# mains_relay_modem.net
KiCad netlist of a schematic drawn in EAGLE
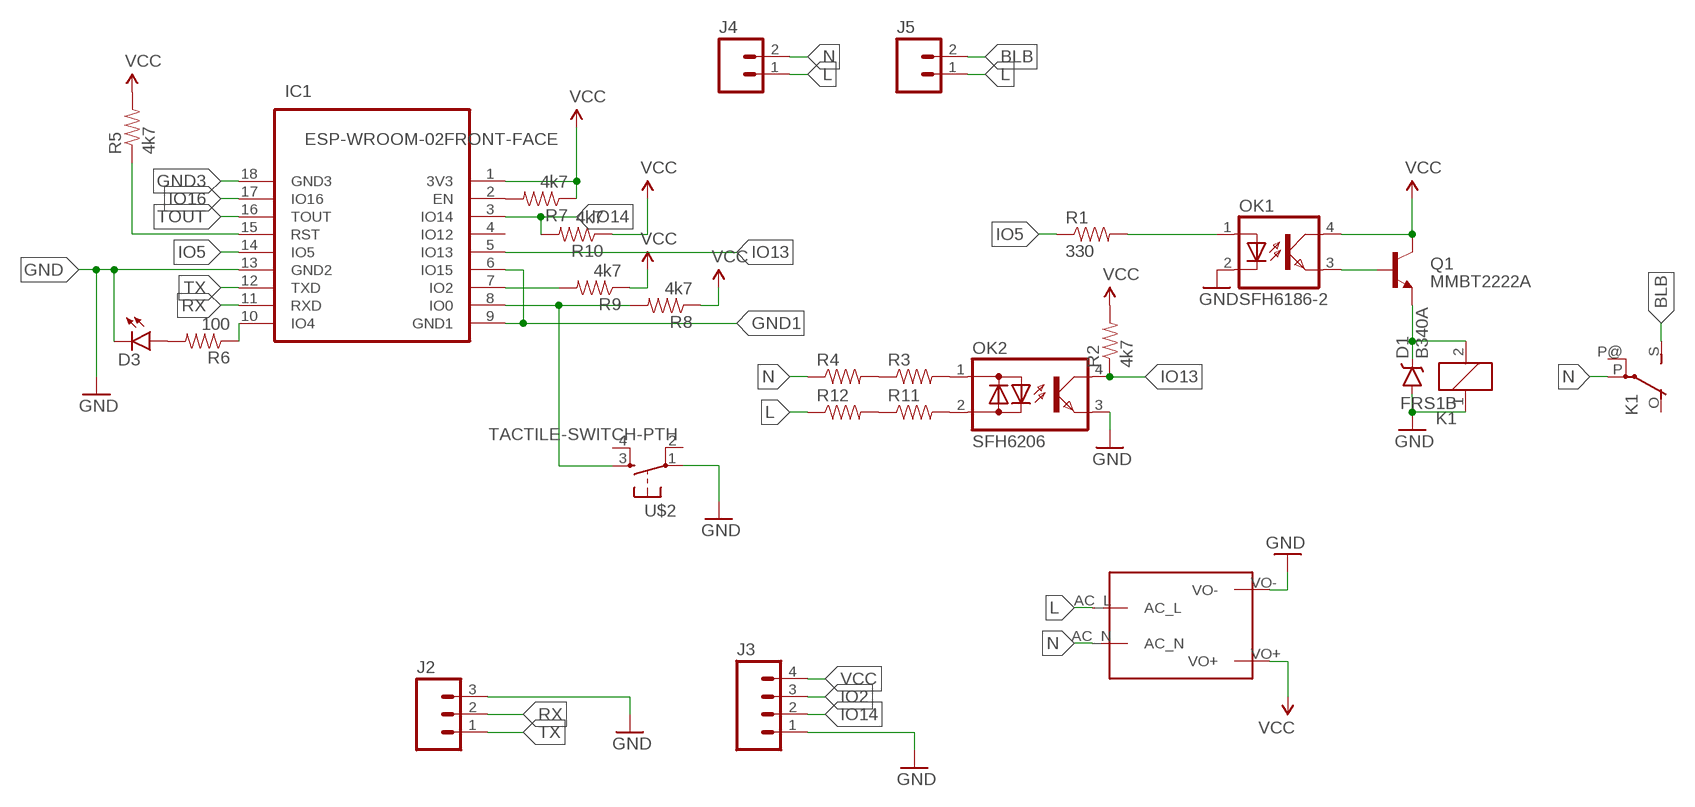
[diagram p0: schematic, sheet 1]

(export (version "E")
  (design (tool "Eeschema 10.0.6"))
  (components
    (comp (ref "D1")
      (value "B340A")
      (footprint "eagle-import:SMA-DIODE")
      (libsource (lib "eagle-import") (part "DIODE-SCHOTTKY-B340A"))
    )
    (comp (ref "D3")
      (value "LED3MM")
      (footprint "eagle-import:LED3MM")
      (libsource (lib "eagle-import") (part "LED3MM"))
    )
    (comp (ref "IC1")
      (value "ESP-WROOM-02FRONT-FACE")
      (footprint "eagle-import:FRONT-FACE")
      (libsource (lib "eagle-import") (part "ESP-WROOM-02FRONT-FACE"))
    )
    (comp (ref "J2")
      (value "M03PTH")
      (footprint "eagle-import:1X03")
      (libsource (lib "eagle-import") (part "M03PTH"))
    )
    (comp (ref "J3")
      (value "M04NO_SILK_ALL_ROUND")
      (footprint "eagle-import:1X04_NO_SILK_ALL_ROUND")
      (libsource (lib "eagle-import") (part "M04NO_SILK_ALL_ROUND"))
    )
    (comp (ref "J4")
      (value "M025MM")
      (footprint "eagle-import:SCREWTERMINAL-5MM-2")
      (libsource (lib "eagle-import") (part "M025MM"))
    )
    (comp (ref "J5")
      (value "M025MM")
      (footprint "eagle-import:SCREWTERMINAL-5MM-2")
      (libsource (lib "eagle-import") (part "M025MM"))
    )
    (comp (ref "K1")
      (value "FRS1B")
      (footprint "eagle-import:FRS1B")
      (libsource (lib "eagle-import") (part "FRS1B"))
    )
    (comp (ref "OK1")
      (value "SFH6186-2")
      (footprint "eagle-import:SMD4")
      (libsource (lib "eagle-import") (part "SFH618?6-2"))
    )
    (comp (ref "OK2")
      (value "SFH6206")
      (footprint "eagle-import:DIL4-SMD")
      (libsource (lib "eagle-import") (part "SFH6206"))
    )
    (comp (ref "Q1")
      (value "MMBT2222A")
      (footprint "eagle-import:SOT23-3")
      (libsource (lib "eagle-import") (part "TRANSISTOR_NPNMMBT2222A"))
    )
    (comp (ref "R1")
      (value "330")
      (footprint "eagle-import:0805")
      (libsource (lib "eagle-import") (part "RESISTOR0805-RES"))
    )
    (comp (ref "R2")
      (value "4k7")
      (footprint "eagle-import:0805")
      (libsource (lib "eagle-import") (part "RESISTOR0805-RES"))
    )
    (comp (ref "R3")
      (value "RESISTOR0805-RES")
      (footprint "eagle-import:0805")
      (libsource (lib "eagle-import") (part "RESISTOR0805-RES"))
    )
    (comp (ref "R4")
      (value "RESISTOR0805-RES")
      (footprint "eagle-import:0805")
      (libsource (lib "eagle-import") (part "RESISTOR0805-RES"))
    )
    (comp (ref "R5")
      (value "4k7")
      (footprint "eagle-import:0805")
      (libsource (lib "eagle-import") (part "RESISTOR0805-RES"))
    )
    (comp (ref "R6")
      (value "100")
      (footprint "eagle-import:0805")
      (libsource (lib "eagle-import") (part "RESISTOR0805-RES"))
    )
    (comp (ref "R7")
      (value "4k7")
      (footprint "eagle-import:0805")
      (libsource (lib "eagle-import") (part "RESISTOR0805-RES"))
    )
    (comp (ref "R8")
      (value "4k7")
      (footprint "eagle-import:0805")
      (libsource (lib "eagle-import") (part "RESISTOR0805-RES"))
    )
    (comp (ref "R9")
      (value "4k7")
      (footprint "eagle-import:0805")
      (libsource (lib "eagle-import") (part "RESISTOR0805-RES"))
    )
    (comp (ref "R10")
      (value "4k7")
      (footprint "eagle-import:0805")
      (libsource (lib "eagle-import") (part "RESISTOR0805-RES"))
    )
    (comp (ref "R11")
      (value "RESISTOR0805-RES")
      (footprint "eagle-import:0805")
      (libsource (lib "eagle-import") (part "RESISTOR0805-RES"))
    )
    (comp (ref "R12")
      (value "RESISTOR0805-RES")
      (footprint "eagle-import:0805")
      (libsource (lib "eagle-import") (part "RESISTOR0805-RES"))
    )
    (comp (ref "U$1")
      (value "MAINS_CONVERTERS")
      (footprint "eagle-import:HLK-PM01")
      (libsource (lib "eagle-import") (part "MAINS_CONVERTERS"))
    )
    (comp (ref "U$2")
      (value "TACTILE-SWITCH-PTH")
      (footprint "eagle-import:TAC-SWITCH-PTH")
      (libsource (lib "eagle-import") (part "TACTILE-SWITCH-PTH"))
    )
  )
  (nets
    (net (code "1") (name "BLB") (class "Default")
      (node (ref "J5") (pin "2") (pinfunction "2_2") (pintype "passive"))
      (node (ref "K1") (pin "S") (pinfunction "S_S") (pintype "passive"))
    )
    (net (code "2") (name "GND") (class "Default")
      (node (ref "D1") (pin "A") (pinfunction "A_A") (pintype "passive"))
      (node (ref "D3") (pin "K") (pinfunction "C_K") (pintype "passive"))
      (node (ref "IC1") (pin "13") (pinfunction "GND2_13") (pintype "power_in"))
      (node (ref "J2") (pin "3") (pinfunction "3_3") (pintype "passive"))
      (node (ref "J3") (pin "1") (pinfunction "1_1") (pintype "passive"))
      (node (ref "K1") (pin "1") (pinfunction "1_1") (pintype "passive"))
      (node (ref "OK1") (pin "2") (pinfunction "C_2") (pintype "passive"))
      (node (ref "OK2") (pin "3") (pinfunction "E_3") (pintype "passive"))
      (node (ref "U$1") (pin "VO-") (pinfunction "VO-_VO-") (pintype "output"))
      (node (ref "U$2") (pin "1") (pinfunction "1_1") (pintype "passive"))
    )
    (net (code "3") (name "GND1") (class "Default")
      (node (ref "IC1") (pin "6") (pinfunction "IO15_6") (pintype "bidirectional"))
      (node (ref "IC1") (pin "9") (pinfunction "GND1_9") (pintype "power_in"))
    )
    (net (code "4") (name "GND3") (class "Default")
      (node (ref "IC1") (pin "18") (pinfunction "GND3_18") (pintype "power_in"))
    )
    (net (code "5") (name "IO2") (class "Default")
      (node (ref "IC1") (pin "7") (pinfunction "IO2_7") (pintype "bidirectional"))
      (node (ref "J3") (pin "3") (pinfunction "3_3") (pintype "passive"))
      (node (ref "R9") (pin "2") (pinfunction "2_2") (pintype "passive"))
    )
    (net (code "6") (name "IO5") (class "Default")
      (node (ref "IC1") (pin "14") (pinfunction "IO5_14") (pintype "open_collector"))
      (node (ref "R1") (pin "1") (pinfunction "1_1") (pintype "passive"))
    )
    (net (code "7") (name "IO13") (class "Default")
      (node (ref "IC1") (pin "5") (pinfunction "IO13_5") (pintype "bidirectional"))
      (node (ref "OK2") (pin "4") (pinfunction "C_4") (pintype "passive"))
      (node (ref "R2") (pin "1") (pinfunction "1_1") (pintype "passive"))
    )
    (net (code "8") (name "IO14") (class "Default")
      (node (ref "IC1") (pin "3") (pinfunction "IO14_3") (pintype "bidirectional"))
      (node (ref "J3") (pin "2") (pinfunction "2_2") (pintype "passive"))
      (node (ref "R10") (pin "2") (pinfunction "2_2") (pintype "passive"))
    )
    (net (code "9") (name "IO16") (class "Default")
      (node (ref "IC1") (pin "17") (pinfunction "IO16_17") (pintype "bidirectional"))
    )
    (net (code "10") (name "L") (class "Default")
      (node (ref "J4") (pin "1") (pinfunction "1_1") (pintype "passive"))
      (node (ref "J5") (pin "1") (pinfunction "1_1") (pintype "passive"))
      (node (ref "R12") (pin "1") (pinfunction "1_1") (pintype "passive"))
      (node (ref "U$1") (pin "AC_L") (pinfunction "AC_L_AC_L") (pintype "input"))
    )
    (net (code "11") (name "N") (class "Default")
      (node (ref "J4") (pin "2") (pinfunction "2_2") (pintype "passive"))
      (node (ref "K1") (pin "P") (pinfunction "P_P") (pintype "passive"))
      (node (ref "R4") (pin "1") (pinfunction "1_1") (pintype "passive"))
      (node (ref "U$1") (pin "AC_N") (pinfunction "AC_N_AC_N") (pintype "input"))
    )
    (net (code "12") (name "Net-(D3-PadA)") (class "Default")
      (node (ref "D3") (pin "A") (pinfunction "A_A") (pintype "passive"))
      (node (ref "R6") (pin "2") (pinfunction "2_2") (pintype "passive"))
    )
    (net (code "13") (name "Net-(IC1-EN)") (class "Default")
      (node (ref "IC1") (pin "2") (pinfunction "EN_2") (pintype "bidirectional"))
      (node (ref "R7") (pin "2") (pinfunction "2_2") (pintype "passive"))
    )
    (net (code "14") (name "Net-(IC1-IO0)") (class "Default")
      (node (ref "IC1") (pin "8") (pinfunction "IO0_8") (pintype "bidirectional"))
      (node (ref "R8") (pin "2") (pinfunction "2_2") (pintype "passive"))
      (node (ref "U$2") (pin "3") (pinfunction "3_3") (pintype "passive"))
    )
    (net (code "15") (name "Net-(IC1-IO4)") (class "Default")
      (node (ref "IC1") (pin "10") (pinfunction "IO4_10") (pintype "bidirectional"))
      (node (ref "R6") (pin "1") (pinfunction "1_1") (pintype "passive"))
    )
    (net (code "16") (name "Net-(IC1-RST)") (class "Default")
      (node (ref "IC1") (pin "15") (pinfunction "RST_15") (pintype "bidirectional"))
      (node (ref "R5") (pin "1") (pinfunction "1_1") (pintype "passive"))
    )
    (net (code "17") (name "Net-(OK1-A)") (class "Default")
      (node (ref "OK1") (pin "1") (pinfunction "A_1") (pintype "passive"))
      (node (ref "R1") (pin "2") (pinfunction "2_2") (pintype "passive"))
    )
    (net (code "18") (name "Net-(OK1-EMIT)") (class "Default")
      (node (ref "OK1") (pin "3") (pinfunction "EMIT_3") (pintype "passive"))
      (node (ref "Q1") (pin "1") (pinfunction "B_1") (pintype "passive"))
    )
    (net (code "19") (name "Net-(OK2-AC1)") (class "Default")
      (node (ref "OK2") (pin "1") (pinfunction "AC1_1") (pintype "passive"))
      (node (ref "R3") (pin "2") (pinfunction "2_2") (pintype "passive"))
    )
    (net (code "20") (name "Net-(OK2-AC2)") (class "Default")
      (node (ref "OK2") (pin "2") (pinfunction "AC2_2") (pintype "passive"))
      (node (ref "R11") (pin "2") (pinfunction "2_2") (pintype "passive"))
    )
    (net (code "21") (name "Net-(Q1-E)") (class "Default")
      (node (ref "D1") (pin "C") (pinfunction "C_C") (pintype "passive"))
      (node (ref "K1") (pin "2") (pinfunction "2_2") (pintype "passive"))
      (node (ref "Q1") (pin "2") (pinfunction "E_2") (pintype "passive"))
    )
    (net (code "22") (name "Net-(R3-Pad1)") (class "Default")
      (node (ref "R3") (pin "1") (pinfunction "1_1") (pintype "passive"))
      (node (ref "R4") (pin "2") (pinfunction "2_2") (pintype "passive"))
    )
    (net (code "23") (name "Net-(R11-Pad1)") (class "Default")
      (node (ref "R11") (pin "1") (pinfunction "1_1") (pintype "passive"))
      (node (ref "R12") (pin "2") (pinfunction "2_2") (pintype "passive"))
    )
    (net (code "24") (name "RX") (class "Default")
      (node (ref "IC1") (pin "11") (pinfunction "RXD_11") (pintype "bidirectional"))
      (node (ref "J2") (pin "2") (pinfunction "2_2") (pintype "passive"))
    )
    (net (code "25") (name "TOUT") (class "Default")
      (node (ref "IC1") (pin "16") (pinfunction "TOUT_16") (pintype "bidirectional"))
    )
    (net (code "26") (name "TX") (class "Default")
      (node (ref "IC1") (pin "12") (pinfunction "TXD_12") (pintype "bidirectional"))
      (node (ref "J2") (pin "1") (pinfunction "1_1") (pintype "passive"))
    )
    (net (code "27") (name "VCC") (class "Default")
      (node (ref "IC1") (pin "1") (pinfunction "3V3_1") (pintype "power_in"))
      (node (ref "J3") (pin "4") (pinfunction "4_4") (pintype "passive"))
      (node (ref "OK1") (pin "4") (pinfunction "COL_4") (pintype "passive"))
      (node (ref "Q1") (pin "3") (pinfunction "C_3") (pintype "passive"))
      (node (ref "R10") (pin "1") (pinfunction "1_1") (pintype "passive"))
      (node (ref "R2") (pin "2") (pinfunction "2_2") (pintype "passive"))
      (node (ref "R5") (pin "2") (pinfunction "2_2") (pintype "passive"))
      (node (ref "R7") (pin "1") (pinfunction "1_1") (pintype "passive"))
      (node (ref "R8") (pin "1") (pinfunction "1_1") (pintype "passive"))
      (node (ref "R9") (pin "1") (pinfunction "1_1") (pintype "passive"))
      (node (ref "U$1") (pin "VO+") (pinfunction "VO+_VO+") (pintype "output"))
    )
    (net (code "28") (name "unconnected-(IC1-IO12-Pad4)") (class "Default")
      (node (ref "IC1") (pin "4") (pinfunction "IO12_4") (pintype "bidirectional"))
    )
    (net (code "29") (name "unconnected-(K1-PadO)") (class "Default")
      (node (ref "K1") (pin "O") (pinfunction "O_O") (pintype "passive"))
    )
    (net (code "30") (name "unconnected-(K1B-P-PadP@)") (class "Default")
      (node (ref "K1") (pin "P@") (pinfunction "P_P@") (pintype "passive"))
    )
    (net (code "31") (name "unconnected-(U$2-Pad2)") (class "Default")
      (node (ref "U$2") (pin "2") (pinfunction "2_2") (pintype "passive"))
    )
    (net (code "32") (name "unconnected-(U$2-Pad4)") (class "Default")
      (node (ref "U$2") (pin "4") (pinfunction "4_4") (pintype "passive"))
    )
  )
)
